# Ball_Locator.net
KiCad netlist of a schematic drawn in Altium Designer
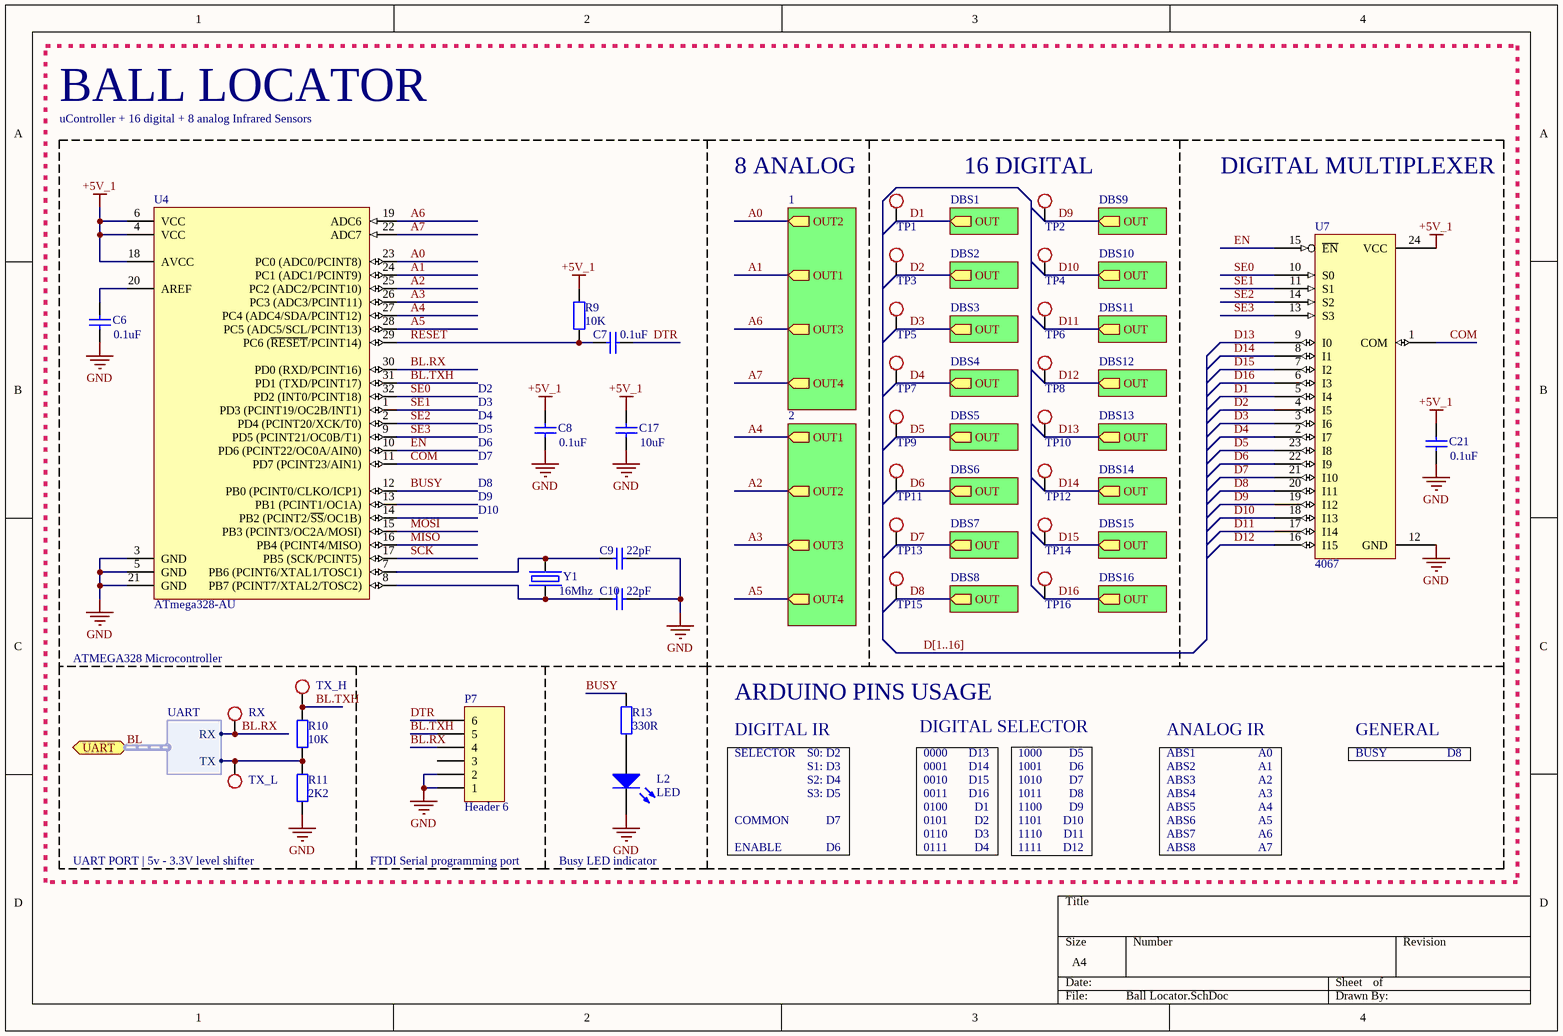
[diagram p0: Ball Locator.SchDoc]

(export (version "E")
  (design (tool "Eeschema 10.0.6"))
  (components
    (comp (ref "C6")
      (value "0.1uF")
      (footprint "C0805")
      (description "Capacitor (Semiconductor SIM Model)")
      (fields (field (name "PUBLISHER") "Altium Limited"))
      (libsource (lib "Miscellaneous Devices") (part "Cap Semi"))
    )
    (comp (ref "C7")
      (value "0.1uF")
      (footprint "C0805")
      (description "Capacitor (Semiconductor SIM Model)")
      (fields (field (name "PUBLISHER") "Altium Limited"))
      (libsource (lib "Miscellaneous Devices") (part "Cap Semi"))
    )
    (comp (ref "C8")
      (value "0.1uF")
      (footprint "C0805")
      (description "Capacitor (Semiconductor SIM Model)")
      (fields (field (name "PUBLISHER") "Altium Limited"))
      (libsource (lib "Miscellaneous Devices") (part "Cap Semi"))
    )
    (comp (ref "C9")
      (value "22pF")
      (footprint "C0805")
      (description "Capacitor (Semiconductor SIM Model)")
      (fields (field (name "PUBLISHER") "Altium Limited"))
      (libsource (lib "Miscellaneous Devices") (part "Cap Semi"))
    )
    (comp (ref "C10")
      (value "22pF")
      (footprint "C0805")
      (description "Capacitor (Semiconductor SIM Model)")
      (fields (field (name "PUBLISHER") "Altium Limited"))
      (libsource (lib "Miscellaneous Devices") (part "Cap Semi"))
    )
    (comp (ref "C17")
      (value "10uF")
      (footprint "C1206")
      (description "Capacitor (Semiconductor SIM Model)")
      (fields (field (name "PUBLISHER") "Altium Limited"))
      (libsource (lib "Miscellaneous Devices") (part "Cap Semi"))
    )
    (comp (ref "C21")
      (value "0.1uF")
      (footprint "C0805")
      (description "Capacitor (Semiconductor SIM Model)")
      (fields (field (name "PUBLISHER") "Altium Limited"))
      (libsource (lib "Miscellaneous Devices") (part "Cap Semi"))
    )
    (comp (ref "L2") (value "LED") (footprint "LED0805") (libsource (lib "CustomLibrary") (part "LED")))
    (comp (ref "P7")
      (value "Header 6")
      (footprint "HDR1X6")
      (description "Header, 6-Pin")
      (fields (field (name "PUBLISHER") "Altium Limited"))
      (libsource (lib "Miscellaneous Connectors") (part "Header 6"))
    )
    (comp (ref "R9") (value "10K") (footprint "RES1206") (libsource (lib "") (part "RES_1")))
    (comp (ref "R10") (value "10K") (footprint "RES1206") (libsource (lib "CustomLibrary") (part "RES")))
    (comp (ref "R11") (value "2K2") (footprint "RES1206") (libsource (lib "CustomLibrary") (part "RES")))
    (comp (ref "R13") (value "330R") (footprint "RES1206") (libsource (lib "CustomLibrary") (part "RES")))
    (comp (ref "RX")
      (value "Test Point")
      (footprint "TP1")
      (description "Test Point for Osciloscope measurements")
      (libsource (lib "CustomLibrary") (part "Test Point"))
    )
    (comp (ref "TP1")
      (value "Test Point")
      (footprint "TP1")
      (description "Test Point for Osciloscope measurements")
      (libsource (lib "CustomLibrary") (part "Test Point"))
    )
    (comp (ref "TP2")
      (value "Test Point")
      (footprint "TP1")
      (description "Test Point for Osciloscope measurements")
      (libsource (lib "CustomLibrary") (part "Test Point"))
    )
    (comp (ref "TP3")
      (value "Test Point")
      (footprint "TP1")
      (description "Test Point for Osciloscope measurements")
      (libsource (lib "CustomLibrary") (part "Test Point"))
    )
    (comp (ref "TP4")
      (value "Test Point")
      (footprint "TP1")
      (description "Test Point for Osciloscope measurements")
      (libsource (lib "CustomLibrary") (part "Test Point"))
    )
    (comp (ref "TP5")
      (value "Test Point")
      (footprint "TP1")
      (description "Test Point for Osciloscope measurements")
      (libsource (lib "CustomLibrary") (part "Test Point"))
    )
    (comp (ref "TP6")
      (value "Test Point")
      (footprint "TP1")
      (description "Test Point for Osciloscope measurements")
      (libsource (lib "CustomLibrary") (part "Test Point"))
    )
    (comp (ref "TP7")
      (value "Test Point")
      (footprint "TP1")
      (description "Test Point for Osciloscope measurements")
      (libsource (lib "CustomLibrary") (part "Test Point"))
    )
    (comp (ref "TP8")
      (value "Test Point")
      (footprint "TP1")
      (description "Test Point for Osciloscope measurements")
      (libsource (lib "CustomLibrary") (part "Test Point"))
    )
    (comp (ref "TP9")
      (value "Test Point")
      (footprint "TP1")
      (description "Test Point for Osciloscope measurements")
      (libsource (lib "CustomLibrary") (part "Test Point"))
    )
    (comp (ref "TP10")
      (value "Test Point")
      (footprint "TP1")
      (description "Test Point for Osciloscope measurements")
      (libsource (lib "CustomLibrary") (part "Test Point"))
    )
    (comp (ref "TP11")
      (value "Test Point")
      (footprint "TP1")
      (description "Test Point for Osciloscope measurements")
      (libsource (lib "CustomLibrary") (part "Test Point"))
    )
    (comp (ref "TP12")
      (value "Test Point")
      (footprint "TP1")
      (description "Test Point for Osciloscope measurements")
      (libsource (lib "CustomLibrary") (part "Test Point"))
    )
    (comp (ref "TP13")
      (value "Test Point")
      (footprint "TP1")
      (description "Test Point for Osciloscope measurements")
      (libsource (lib "CustomLibrary") (part "Test Point"))
    )
    (comp (ref "TP14")
      (value "Test Point")
      (footprint "TP1")
      (description "Test Point for Osciloscope measurements")
      (libsource (lib "CustomLibrary") (part "Test Point"))
    )
    (comp (ref "TP15")
      (value "Test Point")
      (footprint "TP1")
      (description "Test Point for Osciloscope measurements")
      (libsource (lib "CustomLibrary") (part "Test Point"))
    )
    (comp (ref "TP16")
      (value "Test Point")
      (footprint "TP1")
      (description "Test Point for Osciloscope measurements")
      (libsource (lib "CustomLibrary") (part "Test Point"))
    )
    (comp (ref "TX_H")
      (value "Test Point")
      (footprint "TP1")
      (description "Test Point for Osciloscope measurements")
      (libsource (lib "CustomLibrary") (part "Test Point"))
    )
    (comp (ref "TX_L")
      (value "Test Point")
      (footprint "TP1")
      (description "Test Point for Osciloscope measurements")
      (libsource (lib "CustomLibrary") (part "Test Point"))
    )
    (comp (ref "U4")
      (value "ATmega328-AU")
      (footprint "32A_N")
      (fields (field (name "PUBLISHER") "Altium Limited"))
      (libsource (lib "Atmel Microcontroller 8-Bit megaAVR") (part "ATmega328-AU"))
    )
    (comp (ref "U7")
      (value "4067")
      (footprint "SSOP-24")
      (description "MUX-74HC4067")
      (libsource (lib "CustomLibrary") (part "MUX-74HC4067"))
    )
    (comp (ref "Y1")
      (value "16Mhz")
      (footprint "OSC-2-PIN-TH")
      (description "2 pin oscilator")
      (libsource (lib "CustomLibrary") (part "OSC-2-PIN"))
    )
  )
  (nets
    (net (code "2") (name "+5V_1") (class "Default")
      (node (ref "C17") (pin "2") (pinfunction "2_2") (pintype "passive"))
      (node (ref "C21") (pin "2") (pinfunction "2_2") (pintype "passive"))
      (node (ref "C8") (pin "2") (pinfunction "2_2") (pintype "passive"))
      (node (ref "R9") (pin "1") (pinfunction "1_1") (pintype "passive"))
      (node (ref "U4") (pin "18") (pinfunction "AVCC_18") (pintype "power_in"))
      (node (ref "U4") (pin "4") (pinfunction "VCC_4") (pintype "power_in"))
      (node (ref "U4") (pin "6") (pinfunction "VCC_6") (pintype "power_in"))
      (node (ref "U7") (pin "24") (pinfunction "VCC_24") (pintype "power_in"))
    )
    (net (code "3") (name "/A0") (class "Default")
      (node (ref "U4") (pin "23") (pinfunction "PC0_(ADC0/PCINT8)_23") (pintype "bidirectional"))
    )
    (net (code "4") (name "/A1") (class "Default")
      (node (ref "U4") (pin "24") (pinfunction "PC1_(ADC1/PCINT9)_24") (pintype "bidirectional"))
    )
    (net (code "5") (name "/A2") (class "Default")
      (node (ref "U4") (pin "25") (pinfunction "PC2_(ADC2/PCINT10)_25") (pintype "bidirectional"))
    )
    (net (code "6") (name "/A3") (class "Default")
      (node (ref "U4") (pin "26") (pinfunction "PC3_(ADC3/PCINT11)_26") (pintype "bidirectional"))
    )
    (net (code "7") (name "/A4") (class "Default")
      (node (ref "U4") (pin "27") (pinfunction "PC4_(ADC4/SDA/PCINT12)_27") (pintype "bidirectional"))
    )
    (net (code "8") (name "/A5") (class "Default")
      (node (ref "U4") (pin "28") (pinfunction "PC5_(ADC5/SCL/PCINT13)_28") (pintype "bidirectional"))
    )
    (net (code "9") (name "/A6") (class "Default")
      (node (ref "U4") (pin "19") (pinfunction "ADC6_19") (pintype "input"))
    )
    (net (code "10") (name "/A7") (class "Default")
      (node (ref "U4") (pin "22") (pinfunction "ADC7_22") (pintype "input"))
    )
    (net (code "11") (name "/BL.RX") (class "Default")
      (node (ref "P7") (pin "4") (pinfunction "4_4") (pintype "passive"))
      (node (ref "RX") (pin "1") (pinfunction "1_1") (pintype "passive"))
      (node (ref "U4") (pin "30") (pinfunction "PD0_(RXD/PCINT16)_30") (pintype "bidirectional"))
    )
    (net (code "12") (name "/BL.TXH") (class "Default")
      (node (ref "P7") (pin "5") (pinfunction "5_5") (pintype "passive"))
      (node (ref "R10") (pin "2") (pinfunction "2_2") (pintype "passive"))
      (node (ref "TX_H") (pin "1") (pinfunction "1_1") (pintype "passive"))
      (node (ref "U4") (pin "31") (pinfunction "PD1_(TXD/PCINT17)_31") (pintype "bidirectional"))
    )
    (net (code "14") (name "/BUSY") (class "Default")
      (node (ref "R13") (pin "2") (pinfunction "2_2") (pintype "passive"))
      (node (ref "U4") (pin "12") (pinfunction "PB0_(PCINT0/CLKO/ICP1)_12") (pintype "bidirectional"))
    )
    (net (code "15") (name "/COM") (class "Default")
      (node (ref "U4") (pin "11") (pinfunction "PD7_(PCINT23/AIN1)_11") (pintype "bidirectional"))
      (node (ref "U7") (pin "1") (pinfunction "COM_1") (pintype "bidirectional"))
    )
    (net (code "16") (name "/D1") (class "Default")
      (node (ref "TP1") (pin "1") (pinfunction "1_1") (pintype "passive"))
      (node (ref "U7") (pin "5") (pinfunction "I4_5") (pintype "bidirectional"))
    )
    (net (code "17") (name "/D2") (class "Default")
      (node (ref "TP3") (pin "1") (pinfunction "1_1") (pintype "passive"))
      (node (ref "U7") (pin "4") (pinfunction "I5_4") (pintype "bidirectional"))
    )
    (net (code "18") (name "/D3") (class "Default")
      (node (ref "TP5") (pin "1") (pinfunction "1_1") (pintype "passive"))
      (node (ref "U7") (pin "3") (pinfunction "I6_3") (pintype "bidirectional"))
    )
    (net (code "19") (name "/D4") (class "Default")
      (node (ref "TP7") (pin "1") (pinfunction "1_1") (pintype "passive"))
      (node (ref "U7") (pin "2") (pinfunction "I7_2") (pintype "bidirectional"))
    )
    (net (code "20") (name "/D5") (class "Default")
      (node (ref "TP9") (pin "1") (pinfunction "1_1") (pintype "passive"))
      (node (ref "U7") (pin "23") (pinfunction "I8_23") (pintype "bidirectional"))
    )
    (net (code "21") (name "/D6") (class "Default")
      (node (ref "TP11") (pin "1") (pinfunction "1_1") (pintype "passive"))
      (node (ref "U7") (pin "22") (pinfunction "I9_22") (pintype "bidirectional"))
    )
    (net (code "22") (name "/D7") (class "Default")
      (node (ref "TP13") (pin "1") (pinfunction "1_1") (pintype "passive"))
      (node (ref "U7") (pin "21") (pinfunction "I10_21") (pintype "bidirectional"))
    )
    (net (code "23") (name "/D8") (class "Default")
      (node (ref "TP15") (pin "1") (pinfunction "1_1") (pintype "passive"))
      (node (ref "U7") (pin "20") (pinfunction "I11_20") (pintype "bidirectional"))
    )
    (net (code "24") (name "/D9") (class "Default")
      (node (ref "TP2") (pin "1") (pinfunction "1_1") (pintype "passive"))
      (node (ref "U7") (pin "19") (pinfunction "I12_19") (pintype "bidirectional"))
    )
    (net (code "25") (name "/D10") (class "Default")
      (node (ref "TP4") (pin "1") (pinfunction "1_1") (pintype "passive"))
      (node (ref "U7") (pin "18") (pinfunction "I13_18") (pintype "bidirectional"))
    )
    (net (code "26") (name "/D11") (class "Default")
      (node (ref "TP6") (pin "1") (pinfunction "1_1") (pintype "passive"))
      (node (ref "U7") (pin "17") (pinfunction "I14_17") (pintype "bidirectional"))
    )
    (net (code "27") (name "/D12") (class "Default")
      (node (ref "TP8") (pin "1") (pinfunction "1_1") (pintype "passive"))
      (node (ref "U7") (pin "16") (pinfunction "I15_16") (pintype "bidirectional"))
    )
    (net (code "28") (name "/D13") (class "Default")
      (node (ref "TP10") (pin "1") (pinfunction "1_1") (pintype "passive"))
      (node (ref "U7") (pin "9") (pinfunction "I0_9") (pintype "bidirectional"))
    )
    (net (code "29") (name "/D14") (class "Default")
      (node (ref "TP12") (pin "1") (pinfunction "1_1") (pintype "passive"))
      (node (ref "U7") (pin "8") (pinfunction "I1_8") (pintype "bidirectional"))
    )
    (net (code "30") (name "/D15") (class "Default")
      (node (ref "TP14") (pin "1") (pinfunction "1_1") (pintype "passive"))
      (node (ref "U7") (pin "7") (pinfunction "I2_7") (pintype "bidirectional"))
    )
    (net (code "31") (name "/D16") (class "Default")
      (node (ref "TP16") (pin "1") (pinfunction "1_1") (pintype "passive"))
      (node (ref "U7") (pin "6") (pinfunction "I3_6") (pintype "bidirectional"))
    )
    (net (code "32") (name "/DTR") (class "Default")
      (node (ref "C7") (pin "2") (pinfunction "2_2") (pintype "passive"))
      (node (ref "P7") (pin "6") (pinfunction "6_6") (pintype "passive"))
    )
    (net (code "34") (name "/EN") (class "Default")
      (node (ref "U4") (pin "10") (pinfunction "PD6_(PCINT22/OC0A/AIN0)_10") (pintype "bidirectional"))
      (node (ref "U7") (pin "15") (pinfunction "~{EN}_15") (pintype "input"))
    )
    (net (code "35") (name "/MISO") (class "Default")
      (node (ref "U4") (pin "16") (pinfunction "PB4_(PCINT4/MISO)_16") (pintype "bidirectional"))
    )
    (net (code "36") (name "/MOSI") (class "Default")
      (node (ref "U4") (pin "15") (pinfunction "PB3_(PCINT3/OC2A/MOSI)_15") (pintype "bidirectional"))
    )
    (net (code "37") (name "/RESET") (class "Default")
      (node (ref "C7") (pin "1") (pinfunction "1_1") (pintype "passive"))
      (node (ref "R9") (pin "2") (pinfunction "2_2") (pintype "passive"))
      (node (ref "U4") (pin "29") (pinfunction "PC6_(~{RESET}/PCINT14)_29") (pintype "bidirectional"))
    )
    (net (code "38") (name "/SCK") (class "Default")
      (node (ref "U4") (pin "17") (pinfunction "PB5_(SCK/PCINT5)_17") (pintype "bidirectional"))
    )
    (net (code "39") (name "/SE0") (class "Default")
      (node (ref "U4") (pin "32") (pinfunction "PD2_(INT0/PCINT18)_32") (pintype "bidirectional"))
      (node (ref "U7") (pin "10") (pinfunction "S0_10") (pintype "input"))
    )
    (net (code "40") (name "/SE1") (class "Default")
      (node (ref "U4") (pin "1") (pinfunction "PD3_(PCINT19/OC2B/INT1)_1") (pintype "bidirectional"))
      (node (ref "U7") (pin "11") (pinfunction "S1_11") (pintype "input"))
    )
    (net (code "41") (name "/SE2") (class "Default")
      (node (ref "U4") (pin "2") (pinfunction "PD4_(PCINT20/XCK/T0)_2") (pintype "bidirectional"))
      (node (ref "U7") (pin "14") (pinfunction "S2_14") (pintype "input"))
    )
    (net (code "42") (name "/SE3") (class "Default")
      (node (ref "U4") (pin "9") (pinfunction "PD5_(PCINT21/OC0B/T1)_9") (pintype "bidirectional"))
      (node (ref "U7") (pin "13") (pinfunction "S3_13") (pintype "input"))
    )
    (net (code "43") (name "GND") (class "Default")
      (node (ref "C10") (pin "2") (pinfunction "2_2") (pintype "passive"))
      (node (ref "C17") (pin "1") (pinfunction "1_1") (pintype "passive"))
      (node (ref "C21") (pin "1") (pinfunction "1_1") (pintype "passive"))
      (node (ref "C6") (pin "1") (pinfunction "1_1") (pintype "passive"))
      (node (ref "C8") (pin "1") (pinfunction "1_1") (pintype "passive"))
      (node (ref "C9") (pin "2") (pinfunction "2_2") (pintype "passive"))
      (node (ref "L2") (pin "2") (pinfunction "K_2") (pintype "passive"))
      (node (ref "P7") (pin "1") (pinfunction "1_1") (pintype "passive"))
      (node (ref "P7") (pin "2") (pinfunction "2_2") (pintype "passive"))
      (node (ref "R11") (pin "1") (pinfunction "1_1") (pintype "passive"))
      (node (ref "U4") (pin "21") (pinfunction "GND_21") (pintype "power_in"))
      (node (ref "U4") (pin "3") (pinfunction "GND_3") (pintype "power_in"))
      (node (ref "U4") (pin "5") (pinfunction "GND_5") (pintype "power_in"))
      (node (ref "U7") (pin "12") (pinfunction "GND_12") (pintype "power_in"))
    )
    (net (code "44") (name "Net-(L2-A)") (class "Default")
      (node (ref "L2") (pin "1") (pinfunction "A_1") (pintype "passive"))
      (node (ref "R13") (pin "1") (pinfunction "1_1") (pintype "passive"))
    )
    (net (code "45") (name "Net-(R10-Pad1)") (class "Default")
      (node (ref "R10") (pin "1") (pinfunction "1_1") (pintype "passive"))
      (node (ref "R11") (pin "2") (pinfunction "2_2") (pintype "passive"))
      (node (ref "TX_L") (pin "1") (pinfunction "1_1") (pintype "passive"))
    )
    (net (code "46") (name "Net-(U4-AREF)") (class "Default")
      (node (ref "C6") (pin "2") (pinfunction "2_2") (pintype "passive"))
      (node (ref "U4") (pin "20") (pinfunction "AREF_20") (pintype "passive"))
    )
    (net (code "47") (name "Net-(U4-PB6_(PCINT6{slash}XTAL1{slash}TOSC1))") (class "Default")
      (node (ref "C9") (pin "1") (pinfunction "1_1") (pintype "passive"))
      (node (ref "U4") (pin "7") (pinfunction "PB6_(PCINT6/XTAL1/TOSC1)_7") (pintype "bidirectional"))
      (node (ref "Y1") (pin "1") (pinfunction "1_1") (pintype "passive"))
    )
    (net (code "48") (name "Net-(U4-PB7_(PCINT7{slash}XTAL2{slash}TOSC2))") (class "Default")
      (node (ref "C10") (pin "1") (pinfunction "1_1") (pintype "passive"))
      (node (ref "U4") (pin "8") (pinfunction "PB7_(PCINT7/XTAL2/TOSC2)_8") (pintype "bidirectional"))
      (node (ref "Y1") (pin "2") (pinfunction "2_2") (pintype "passive"))
    )
    (net (code "49") (name "unconnected-(P7-Pad3)") (class "Default")
      (node (ref "P7") (pin "3") (pinfunction "3_3") (pintype "passive"))
    )
    (net (code "50") (name "unconnected-(U4-PB1_(PCINT1{slash}OC1A)-Pad13)") (class "Default")
      (node (ref "U4") (pin "13") (pinfunction "PB1_(PCINT1/OC1A)_13") (pintype "bidirectional"))
    )
    (net (code "51") (name "unconnected-(U4-PB2_(PCINT2{slash}~{SS}{slash}OC1B)-Pad14)") (class "Default")
      (node (ref "U4") (pin "14") (pinfunction "PB2_(PCINT2/~{SS}/OC1B)_14") (pintype "bidirectional"))
    )
  )
)
